# 15_GPIOs_2.net
KiCad netlist of a schematic drawn in Altium Designer
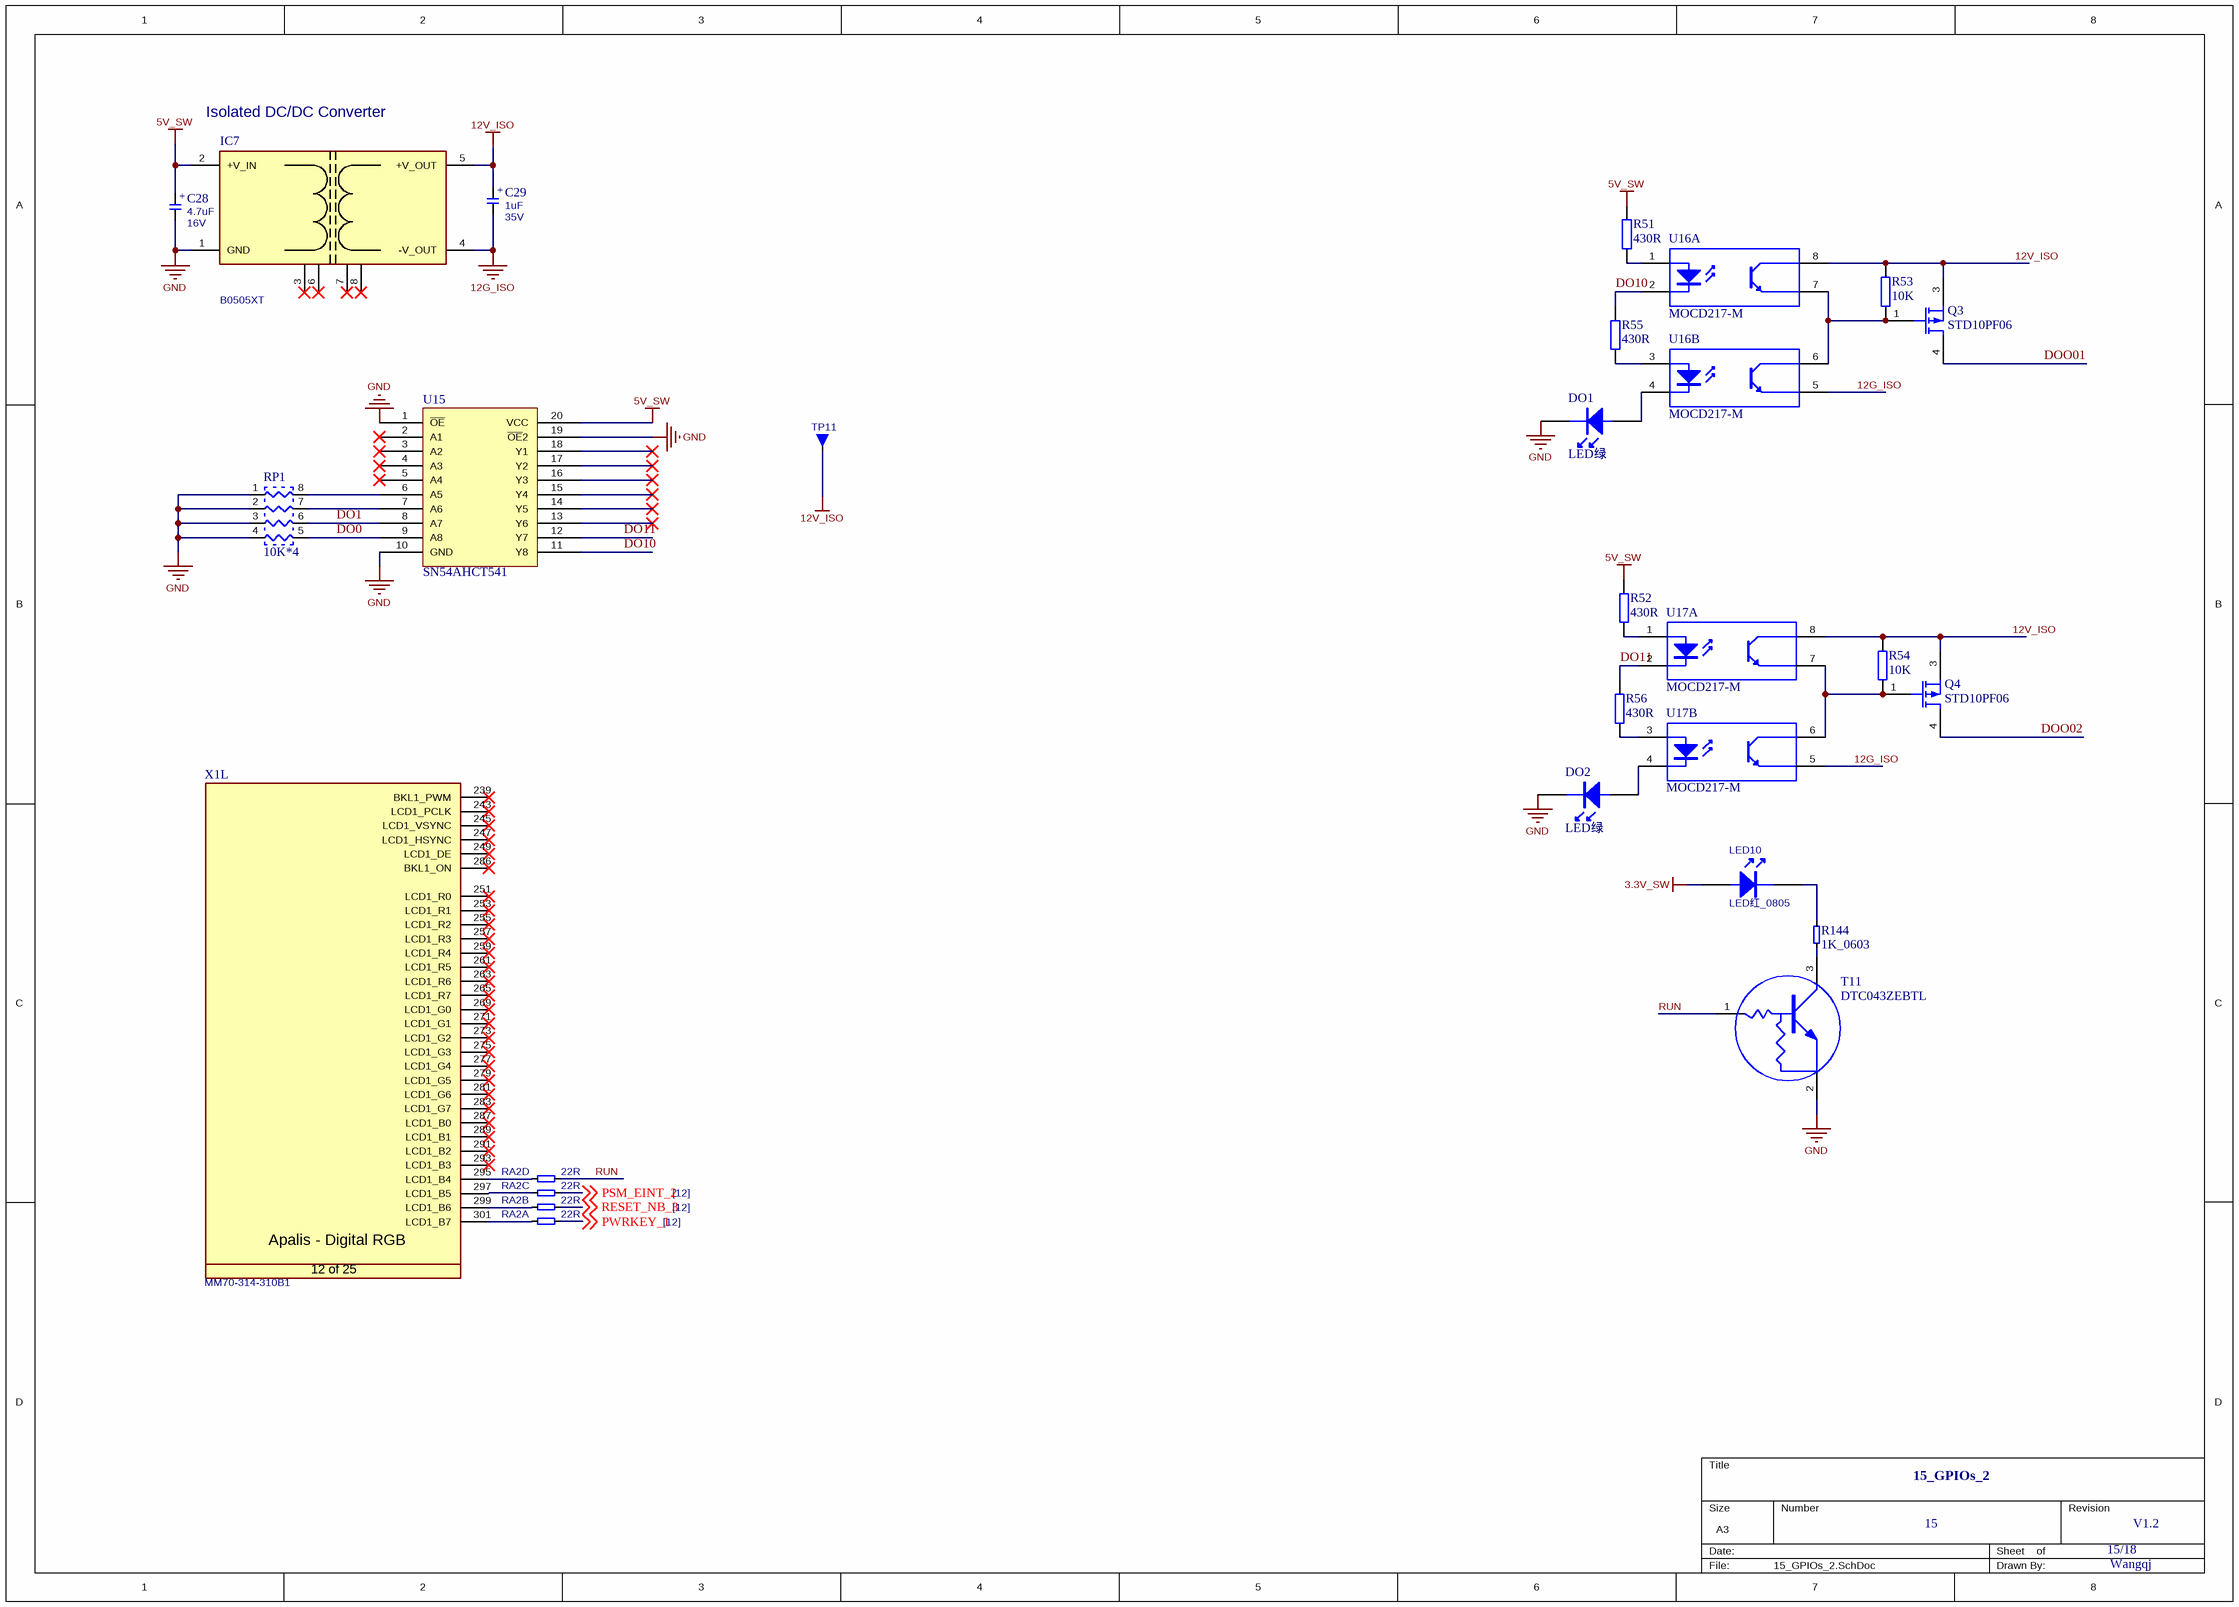
[diagram p0: 15_GPIOs_2.SchDoc]

(export (version "E")
  (design (tool "Eeschema 10.0.6"))
  (components
    (comp (ref "C28")
      (value "4.7uF")
      (footprint "T_CAPMP3216X180N")
      (description "Capacitor TA 4.7uF 16V 10% 3216")
      (fields (field (name "TOLERANCE") "10%") (field (name "RATING") "16V"))
      (libsource (lib "Apalis Evaluation Board") (part "C-4.7uF-16V-10%-3216-TA"))
    )
    (comp (ref "C29")
      (value "1uF")
      (footprint "T_CAPMP3216X180N")
      (description "Capacitor TA 1uF 35V 20% 3216")
      (fields (field (name "TOLERANCE") "20%") (field (name "RATING") "35V"))
      (libsource (lib "Apalis Evaluation Board") (part "C-1uF-16V-10%-3216-TA"))
    )
    (comp (ref "DO1")
      (value "LED绿")
      (footprint "LC-0805_LED_S3")
      (description "0805LED绿")
      (libsource (lib "*") (part "LED"))
    )
    (comp (ref "DO2")
      (value "LED绿")
      (footprint "LC-0805_LED_S3")
      (description "0805LED绿")
      (libsource (lib "*") (part "LED"))
    )
    (comp (ref "IC7")
      (value "B0505XT-1W")
      (footprint "MORNSUN_B0305XT-1W_SMD")
      (description "MORNSUN Isolated DC/DC Converter")
      (fields (field (name "MANUFACTURER PART NO.") "B0505XT"))
      (libsource (lib "Apalis Evaluation Board") (part "IC-MORNSUN-B0505XT-SMD"))
    )
    (comp (ref "LED10")
      (value "LED红_0805")
      (footprint "LC-0805_LED_S3")
      (description "0805LED绿")
      (libsource (lib "*") (part "LED"))
    )
    (comp (ref "Q3")
      (value "STD10PF06")
      (footprint "DPAK")
      (description "P-Channel MOSFET")
      (fields (field (name "PUBLISHER") "Altium Limited"))
      (libsource (lib "CCS11") (part "MOSFET-P1"))
    )
    (comp (ref "Q4")
      (value "STD10PF06")
      (footprint "DPAK")
      (description "P-Channel MOSFET")
      (fields (field (name "PUBLISHER") "Altium Limited"))
      (libsource (lib "CCS11") (part "MOSFET-P1"))
    )
    (comp (ref "R51")
      (value "430R")
      (footprint "0805R")
      (description "贴片电阻")
      (libsource (lib "*") (part "RES2"))
    )
    (comp (ref "R52")
      (value "430R")
      (footprint "0805R")
      (description "贴片电阻")
      (libsource (lib "*") (part "RES2"))
    )
    (comp (ref "R53")
      (value "10K")
      (footprint "0805R")
      (description "贴片电阻")
      (libsource (lib "*") (part "RES2"))
    )
    (comp (ref "R54")
      (value "10K")
      (footprint "0805R")
      (description "贴片电阻")
      (libsource (lib "*") (part "RES2"))
    )
    (comp (ref "R55")
      (value "430R")
      (footprint "0805R")
      (description "贴片电阻")
      (libsource (lib "*") (part "RES2"))
    )
    (comp (ref "R56")
      (value "430R")
      (footprint "0805R")
      (description "贴片电阻")
      (libsource (lib "*") (part "RES2"))
    )
    (comp (ref "R144")
      (value "1K_0603")
      (footprint "T_RESC0603X30N")
      (description "Resistor 1 Kohm 63mW 5% 0603")
      (fields (field (name "TOLERANCE") "5%"))
      (libsource (lib "Apalis Evaluation Board") (part "R-1KR-63mW-5%-0603"))
    )
    (comp (ref "RA2")
      (value "22R")
      (footprint "T_Resistor_Array_X4")
      (description "Resistor Array 22 R 63mW 5% 1206")
      (fields (field (name "TOLERANCE") "5%"))
      (libsource (lib "Apalis Evaluation Board") (part "RA-22R-63mW-5%-1206-div"))
    )
    (comp (ref "RP1")
      (value "10K*4")
      (footprint "CN4")
      (description "贴片排阻")
      (libsource (lib "JCC08V1_0") (part "RP_0.S4"))
    )
    (comp (ref "T11")
      (value "DTC043ZEBTL")
      (footprint "SOT-416FL")
      (description "Bias Resistor Build-in NPN Transistor")
      (libsource (lib "Apalis Evaluation Board") (part "NPN_Bias_Resistor"))
    )
    (comp (ref "TP11")
      (value "Testpin")
      (footprint "T_TP-THT")
      (description "Testpin TH")
      (libsource (lib "Apalis Evaluation Board") (part "Testpin"))
    )
    (comp (ref "U15")
      (value "SN54AHCT541")
      (footprint "TSSOP-20")
      (libsource (lib "CCS1.0") (part "SN54AHCT541"))
    )
    (comp (ref "U16") (value "MOCD217-M") (footprint "HCPL0601") (libsource (lib "CCS10") (part "MOCD217")))
    (comp (ref "U17") (value "MOCD217-M") (footprint "HCPL0601") (libsource (lib "CCS10") (part "MOCD217")))
    (comp (ref "X1")
      (value "CON-JAE-MM70-314-310B1-314-0.5mm")
      (footprint "T_JAE_MM70-314-310B1")
      (description "MXM3 Connector")
      (fields (field (name "MANUFACTURER PART NO.") "MM70-314-310B1"))
      (libsource (lib "Apalis Evaluation Board") (part "CON-JAE-MM70-314-310B1-314-0.5mm"))
    )
  )
  (nets
    (net (code "1") (name "/DO0") (class "Default")
      (node (ref "RP1") (pin "5") (pinfunction "R_5") (pintype "passive"))
      (node (ref "U15") (pin "9") (pinfunction "A8_9") (pintype "passive"))
    )
    (net (code "2") (name "/DO1") (class "Default")
      (node (ref "RP1") (pin "6") (pinfunction "R_6") (pintype "passive"))
      (node (ref "U15") (pin "8") (pinfunction "A7_8") (pintype "passive"))
    )
    (net (code "3") (name "/DO10") (class "Default")
      (node (ref "R55") (pin "2") (pinfunction "2_2") (pintype "passive"))
      (node (ref "U15") (pin "11") (pinfunction "Y8_11") (pintype "passive"))
      (node (ref "U16") (pin "2") (pinfunction "1-_2") (pintype "passive"))
    )
    (net (code "4") (name "/DO11") (class "Default")
      (node (ref "R56") (pin "2") (pinfunction "2_2") (pintype "passive"))
      (node (ref "U15") (pin "12") (pinfunction "Y7_12") (pintype "passive"))
      (node (ref "U17") (pin "2") (pinfunction "1-_2") (pintype "passive"))
    )
    (net (code "5") (name "/DOO01") (class "Default")
      (node (ref "Q3") (pin "4") (pinfunction "D_4") (pintype "passive"))
    )
    (net (code "6") (name "/DOO02") (class "Default")
      (node (ref "Q4") (pin "4") (pinfunction "D_4") (pintype "passive"))
    )
    (net (code "7") (name "/RUN") (class "Default")
      (node (ref "RA2") (pin "8") (pinfunction "8_8") (pintype "passive"))
      (node (ref "T11") (pin "1") (pinfunction "B_1") (pintype "passive"))
    )
    (net (code "8") (name "3.3V_SW") (class "Default")
      (node (ref "LED10") (pin "A") (pinfunction "1_A") (pintype "passive"))
    )
    (net (code "9") (name "5V_SW") (class "Default")
      (node (ref "C28") (pin "1") (pinfunction "1_1") (pintype "passive"))
      (node (ref "IC7") (pin "2") (pinfunction "+V_IN_2") (pintype "power_in"))
      (node (ref "R51") (pin "1") (pinfunction "1_1") (pintype "passive"))
      (node (ref "R52") (pin "1") (pinfunction "1_1") (pintype "passive"))
      (node (ref "U15") (pin "20") (pinfunction "VCC_20") (pintype "passive"))
    )
    (net (code "10") (name "12G_ISO") (class "Default")
      (node (ref "C29") (pin "2") (pinfunction "2_2") (pintype "passive"))
      (node (ref "IC7") (pin "4") (pinfunction "-V_OUT_4") (pintype "power_in"))
      (node (ref "U16") (pin "5") (pinfunction "2C_5") (pintype "passive"))
      (node (ref "U17") (pin "5") (pinfunction "2C_5") (pintype "passive"))
    )
    (net (code "11") (name "12V_ISO") (class "Default")
      (node (ref "C29") (pin "1") (pinfunction "1_1") (pintype "passive"))
      (node (ref "IC7") (pin "5") (pinfunction "+V_OUT_5") (pintype "power_in"))
      (node (ref "Q3") (pin "3") (pinfunction "S_3") (pintype "passive"))
      (node (ref "Q4") (pin "3") (pinfunction "S_3") (pintype "passive"))
      (node (ref "R53") (pin "1") (pinfunction "1_1") (pintype "passive"))
      (node (ref "R54") (pin "1") (pinfunction "1_1") (pintype "passive"))
      (node (ref "TP11") (pin "1") (pinfunction "1_1") (pintype "passive"))
      (node (ref "U16") (pin "8") (pinfunction "1E_8") (pintype "passive"))
      (node (ref "U17") (pin "8") (pinfunction "1E_8") (pintype "passive"))
    )
    (net (code "12") (name "GND") (class "Default")
      (node (ref "C28") (pin "2") (pinfunction "2_2") (pintype "passive"))
      (node (ref "DO1") (pin "K") (pinfunction "2_K") (pintype "passive"))
      (node (ref "DO2") (pin "K") (pinfunction "2_K") (pintype "passive"))
      (node (ref "IC7") (pin "1") (pinfunction "GND_1") (pintype "power_in"))
      (node (ref "RP1") (pin "1") (pinfunction "R_1") (pintype "passive"))
      (node (ref "RP1") (pin "2") (pinfunction "R_2") (pintype "passive"))
      (node (ref "RP1") (pin "3") (pinfunction "R_3") (pintype "passive"))
      (node (ref "RP1") (pin "4") (pinfunction "R_4") (pintype "passive"))
      (node (ref "T11") (pin "2") (pinfunction "E_2") (pintype "passive"))
      (node (ref "U15") (pin "1") (pinfunction "~{OE}_1") (pintype "passive"))
      (node (ref "U15") (pin "10") (pinfunction "GND_10") (pintype "passive"))
      (node (ref "U15") (pin "19") (pinfunction "~{OE}2_19") (pintype "passive"))
    )
    (net (code "13") (name "Net-(DO1-1)") (class "Default")
      (node (ref "DO1") (pin "A") (pinfunction "1_A") (pintype "passive"))
      (node (ref "U16") (pin "4") (pinfunction "2-_4") (pintype "passive"))
    )
    (net (code "14") (name "Net-(DO2-1)") (class "Default")
      (node (ref "DO2") (pin "A") (pinfunction "1_A") (pintype "passive"))
      (node (ref "U17") (pin "4") (pinfunction "2-_4") (pintype "passive"))
    )
    (net (code "15") (name "Net-(LED10-2)") (class "Default")
      (node (ref "LED10") (pin "K") (pinfunction "2_K") (pintype "passive"))
      (node (ref "R144") (pin "2") (pinfunction "2_2") (pintype "passive"))
    )
    (net (code "16") (name "Net-(Q3-G)") (class "Default")
      (node (ref "Q3") (pin "1") (pinfunction "G_1") (pintype "passive"))
      (node (ref "R53") (pin "2") (pinfunction "2_2") (pintype "passive"))
      (node (ref "U16") (pin "6") (pinfunction "2E_6") (pintype "passive"))
      (node (ref "U16") (pin "7") (pinfunction "1C_7") (pintype "passive"))
    )
    (net (code "17") (name "Net-(Q4-G)") (class "Default")
      (node (ref "Q4") (pin "1") (pinfunction "G_1") (pintype "passive"))
      (node (ref "R54") (pin "2") (pinfunction "2_2") (pintype "passive"))
      (node (ref "U17") (pin "6") (pinfunction "2E_6") (pintype "passive"))
      (node (ref "U17") (pin "7") (pinfunction "1C_7") (pintype "passive"))
    )
    (net (code "18") (name "Net-(T11-C)") (class "Default")
      (node (ref "R144") (pin "1") (pinfunction "1_1") (pintype "passive"))
      (node (ref "T11") (pin "3") (pinfunction "C_3") (pintype "passive"))
    )
    (net (code "19") (name "Net-(U15-A5)") (class "Default")
      (node (ref "RP1") (pin "8") (pinfunction "R_8") (pintype "passive"))
      (node (ref "U15") (pin "6") (pinfunction "A5_6") (pintype "passive"))
    )
    (net (code "20") (name "Net-(U15-A6)") (class "Default")
      (node (ref "RP1") (pin "7") (pinfunction "R_7") (pintype "passive"))
      (node (ref "U15") (pin "7") (pinfunction "A6_7") (pintype "passive"))
    )
    (net (code "21") (name "Net-(U16A-1+)") (class "Default")
      (node (ref "R51") (pin "2") (pinfunction "2_2") (pintype "passive"))
      (node (ref "U16") (pin "1") (pinfunction "1+_1") (pintype "passive"))
    )
    (net (code "22") (name "Net-(U16B-2+)") (class "Default")
      (node (ref "R55") (pin "1") (pinfunction "1_1") (pintype "passive"))
      (node (ref "U16") (pin "3") (pinfunction "2+_3") (pintype "passive"))
    )
    (net (code "23") (name "Net-(U17A-1+)") (class "Default")
      (node (ref "R52") (pin "2") (pinfunction "2_2") (pintype "passive"))
      (node (ref "U17") (pin "1") (pinfunction "1+_1") (pintype "passive"))
    )
    (net (code "24") (name "Net-(U17B-2+)") (class "Default")
      (node (ref "R56") (pin "1") (pinfunction "1_1") (pintype "passive"))
      (node (ref "U17") (pin "3") (pinfunction "2+_3") (pintype "passive"))
    )
    (net (code "25") (name "Net-(X1L-LCD1_B4)") (class "Default")
      (node (ref "RA2") (pin "4") (pinfunction "4_4") (pintype "passive"))
      (node (ref "X1") (pin "295") (pinfunction "LCD1_B4_295") (pintype "passive"))
    )
    (net (code "26") (name "Net-(X1L-LCD1_B5)") (class "Default")
      (node (ref "RA2") (pin "3") (pinfunction "3_3") (pintype "passive"))
      (node (ref "X1") (pin "297") (pinfunction "LCD1_B5_297") (pintype "passive"))
    )
    (net (code "27") (name "Net-(X1L-LCD1_B6)") (class "Default")
      (node (ref "RA2") (pin "2") (pinfunction "2_2") (pintype "passive"))
      (node (ref "X1") (pin "299") (pinfunction "LCD1_B6_299") (pintype "passive"))
    )
    (net (code "28") (name "Net-(X1L-LCD1_B7)") (class "Default")
      (node (ref "RA2") (pin "1") (pinfunction "1_1") (pintype "passive"))
      (node (ref "X1") (pin "301") (pinfunction "LCD1_B7_301") (pintype "passive"))
    )
    (net (code "29") (name "PSM_EINT_2") (class "Default")
      (node (ref "RA2") (pin "7") (pinfunction "7_7") (pintype "passive"))
    )
    (net (code "30") (name "PWRKEY_1") (class "Default")
      (node (ref "RA2") (pin "5") (pinfunction "5_5") (pintype "passive"))
    )
    (net (code "31") (name "RESET_NB_3") (class "Default")
      (node (ref "RA2") (pin "6") (pinfunction "6_6") (pintype "passive"))
    )
    (net (code "32") (name "unconnected-(IC7-NC-Pad3)") (class "Default")
      (node (ref "IC7") (pin "3") (pinfunction "NC_3") (pintype "passive+no_connect"))
    )
    (net (code "33") (name "unconnected-(IC7-NC-Pad6)") (class "Default")
      (node (ref "IC7") (pin "6") (pinfunction "NC_6") (pintype "passive+no_connect"))
    )
    (net (code "34") (name "unconnected-(IC7-NC-Pad7)") (class "Default")
      (node (ref "IC7") (pin "7") (pinfunction "NC_7") (pintype "passive+no_connect"))
    )
    (net (code "35") (name "unconnected-(IC7-NC-Pad8)") (class "Default")
      (node (ref "IC7") (pin "8") (pinfunction "NC_8") (pintype "passive+no_connect"))
    )
    (net (code "36") (name "unconnected-(U15-A1-Pad2)") (class "Default")
      (node (ref "U15") (pin "2") (pinfunction "A1_2") (pintype "passive+no_connect"))
    )
    (net (code "37") (name "unconnected-(U15-A2-Pad3)") (class "Default")
      (node (ref "U15") (pin "3") (pinfunction "A2_3") (pintype "passive+no_connect"))
    )
    (net (code "38") (name "unconnected-(U15-A3-Pad4)") (class "Default")
      (node (ref "U15") (pin "4") (pinfunction "A3_4") (pintype "passive+no_connect"))
    )
    (net (code "39") (name "unconnected-(U15-A4-Pad5)") (class "Default")
      (node (ref "U15") (pin "5") (pinfunction "A4_5") (pintype "passive+no_connect"))
    )
    (net (code "40") (name "unconnected-(U15-Y1-Pad18)") (class "Default")
      (node (ref "U15") (pin "18") (pinfunction "Y1_18") (pintype "passive+no_connect"))
    )
    (net (code "41") (name "unconnected-(U15-Y2-Pad17)") (class "Default")
      (node (ref "U15") (pin "17") (pinfunction "Y2_17") (pintype "passive+no_connect"))
    )
    (net (code "42") (name "unconnected-(U15-Y3-Pad16)") (class "Default")
      (node (ref "U15") (pin "16") (pinfunction "Y3_16") (pintype "passive+no_connect"))
    )
    (net (code "43") (name "unconnected-(U15-Y4-Pad15)") (class "Default")
      (node (ref "U15") (pin "15") (pinfunction "Y4_15") (pintype "passive+no_connect"))
    )
    (net (code "44") (name "unconnected-(U15-Y5-Pad14)") (class "Default")
      (node (ref "U15") (pin "14") (pinfunction "Y5_14") (pintype "passive+no_connect"))
    )
    (net (code "45") (name "unconnected-(U15-Y6-Pad13)") (class "Default")
      (node (ref "U15") (pin "13") (pinfunction "Y6_13") (pintype "passive+no_connect"))
    )
    (net (code "46") (name "unconnected-(X1L-BKL1_ON-Pad286)") (class "Default")
      (node (ref "X1") (pin "286") (pinfunction "BKL1_ON_286") (pintype "passive+no_connect"))
    )
    (net (code "47") (name "unconnected-(X1L-BKL1_PWM-Pad239)") (class "Default")
      (node (ref "X1") (pin "239") (pinfunction "BKL1_PWM_239") (pintype "passive+no_connect"))
    )
    (net (code "48") (name "unconnected-(X1L-LCD1_B0-Pad287)") (class "Default")
      (node (ref "X1") (pin "287") (pinfunction "LCD1_B0_287") (pintype "passive+no_connect"))
    )
    (net (code "49") (name "unconnected-(X1L-LCD1_B1-Pad289)") (class "Default")
      (node (ref "X1") (pin "289") (pinfunction "LCD1_B1_289") (pintype "passive+no_connect"))
    )
    (net (code "50") (name "unconnected-(X1L-LCD1_B2-Pad291)") (class "Default")
      (node (ref "X1") (pin "291") (pinfunction "LCD1_B2_291") (pintype "passive+no_connect"))
    )
    (net (code "51") (name "unconnected-(X1L-LCD1_B3-Pad293)") (class "Default")
      (node (ref "X1") (pin "293") (pinfunction "LCD1_B3_293") (pintype "passive+no_connect"))
    )
    (net (code "52") (name "unconnected-(X1L-LCD1_DE-Pad249)") (class "Default")
      (node (ref "X1") (pin "249") (pinfunction "LCD1_DE_249") (pintype "passive+no_connect"))
    )
    (net (code "53") (name "unconnected-(X1L-LCD1_G0-Pad269)") (class "Default")
      (node (ref "X1") (pin "269") (pinfunction "LCD1_G0_269") (pintype "passive+no_connect"))
    )
    (net (code "54") (name "unconnected-(X1L-LCD1_G1-Pad271)") (class "Default")
      (node (ref "X1") (pin "271") (pinfunction "LCD1_G1_271") (pintype "passive+no_connect"))
    )
    (net (code "55") (name "unconnected-(X1L-LCD1_G2-Pad273)") (class "Default")
      (node (ref "X1") (pin "273") (pinfunction "LCD1_G2_273") (pintype "passive+no_connect"))
    )
    (net (code "56") (name "unconnected-(X1L-LCD1_G3-Pad275)") (class "Default")
      (node (ref "X1") (pin "275") (pinfunction "LCD1_G3_275") (pintype "passive+no_connect"))
    )
    (net (code "57") (name "unconnected-(X1L-LCD1_G4-Pad277)") (class "Default")
      (node (ref "X1") (pin "277") (pinfunction "LCD1_G4_277") (pintype "passive+no_connect"))
    )
    (net (code "58") (name "unconnected-(X1L-LCD1_G5-Pad279)") (class "Default")
      (node (ref "X1") (pin "279") (pinfunction "LCD1_G5_279") (pintype "passive+no_connect"))
    )
    (net (code "59") (name "unconnected-(X1L-LCD1_G6-Pad281)") (class "Default")
      (node (ref "X1") (pin "281") (pinfunction "LCD1_G6_281") (pintype "passive+no_connect"))
    )
    (net (code "60") (name "unconnected-(X1L-LCD1_G7-Pad283)") (class "Default")
      (node (ref "X1") (pin "283") (pinfunction "LCD1_G7_283") (pintype "passive+no_connect"))
    )
    (net (code "61") (name "unconnected-(X1L-LCD1_HSYNC-Pad247)") (class "Default")
      (node (ref "X1") (pin "247") (pinfunction "LCD1_HSYNC_247") (pintype "passive+no_connect"))
    )
    (net (code "62") (name "unconnected-(X1L-LCD1_PCLK-Pad243)") (class "Default")
      (node (ref "X1") (pin "243") (pinfunction "LCD1_PCLK_243") (pintype "passive+no_connect"))
    )
    (net (code "63") (name "unconnected-(X1L-LCD1_R0-Pad251)") (class "Default")
      (node (ref "X1") (pin "251") (pinfunction "LCD1_R0_251") (pintype "passive+no_connect"))
    )
    (net (code "64") (name "unconnected-(X1L-LCD1_R1-Pad253)") (class "Default")
      (node (ref "X1") (pin "253") (pinfunction "LCD1_R1_253") (pintype "passive+no_connect"))
    )
    (net (code "65") (name "unconnected-(X1L-LCD1_R2-Pad255)") (class "Default")
      (node (ref "X1") (pin "255") (pinfunction "LCD1_R2_255") (pintype "passive+no_connect"))
    )
    (net (code "66") (name "unconnected-(X1L-LCD1_R3-Pad257)") (class "Default")
      (node (ref "X1") (pin "257") (pinfunction "LCD1_R3_257") (pintype "passive+no_connect"))
    )
    (net (code "67") (name "unconnected-(X1L-LCD1_R4-Pad259)") (class "Default")
      (node (ref "X1") (pin "259") (pinfunction "LCD1_R4_259") (pintype "passive+no_connect"))
    )
    (net (code "68") (name "unconnected-(X1L-LCD1_R5-Pad261)") (class "Default")
      (node (ref "X1") (pin "261") (pinfunction "LCD1_R5_261") (pintype "passive+no_connect"))
    )
    (net (code "69") (name "unconnected-(X1L-LCD1_R6-Pad263)") (class "Default")
      (node (ref "X1") (pin "263") (pinfunction "LCD1_R6_263") (pintype "passive+no_connect"))
    )
    (net (code "70") (name "unconnected-(X1L-LCD1_R7-Pad265)") (class "Default")
      (node (ref "X1") (pin "265") (pinfunction "LCD1_R7_265") (pintype "passive+no_connect"))
    )
    (net (code "71") (name "unconnected-(X1L-LCD1_VSYNC-Pad245)") (class "Default")
      (node (ref "X1") (pin "245") (pinfunction "LCD1_VSYNC_245") (pintype "passive+no_connect"))
    )
  )
)
